# Power.net
KiCad netlist of a schematic drawn in Altium Designer
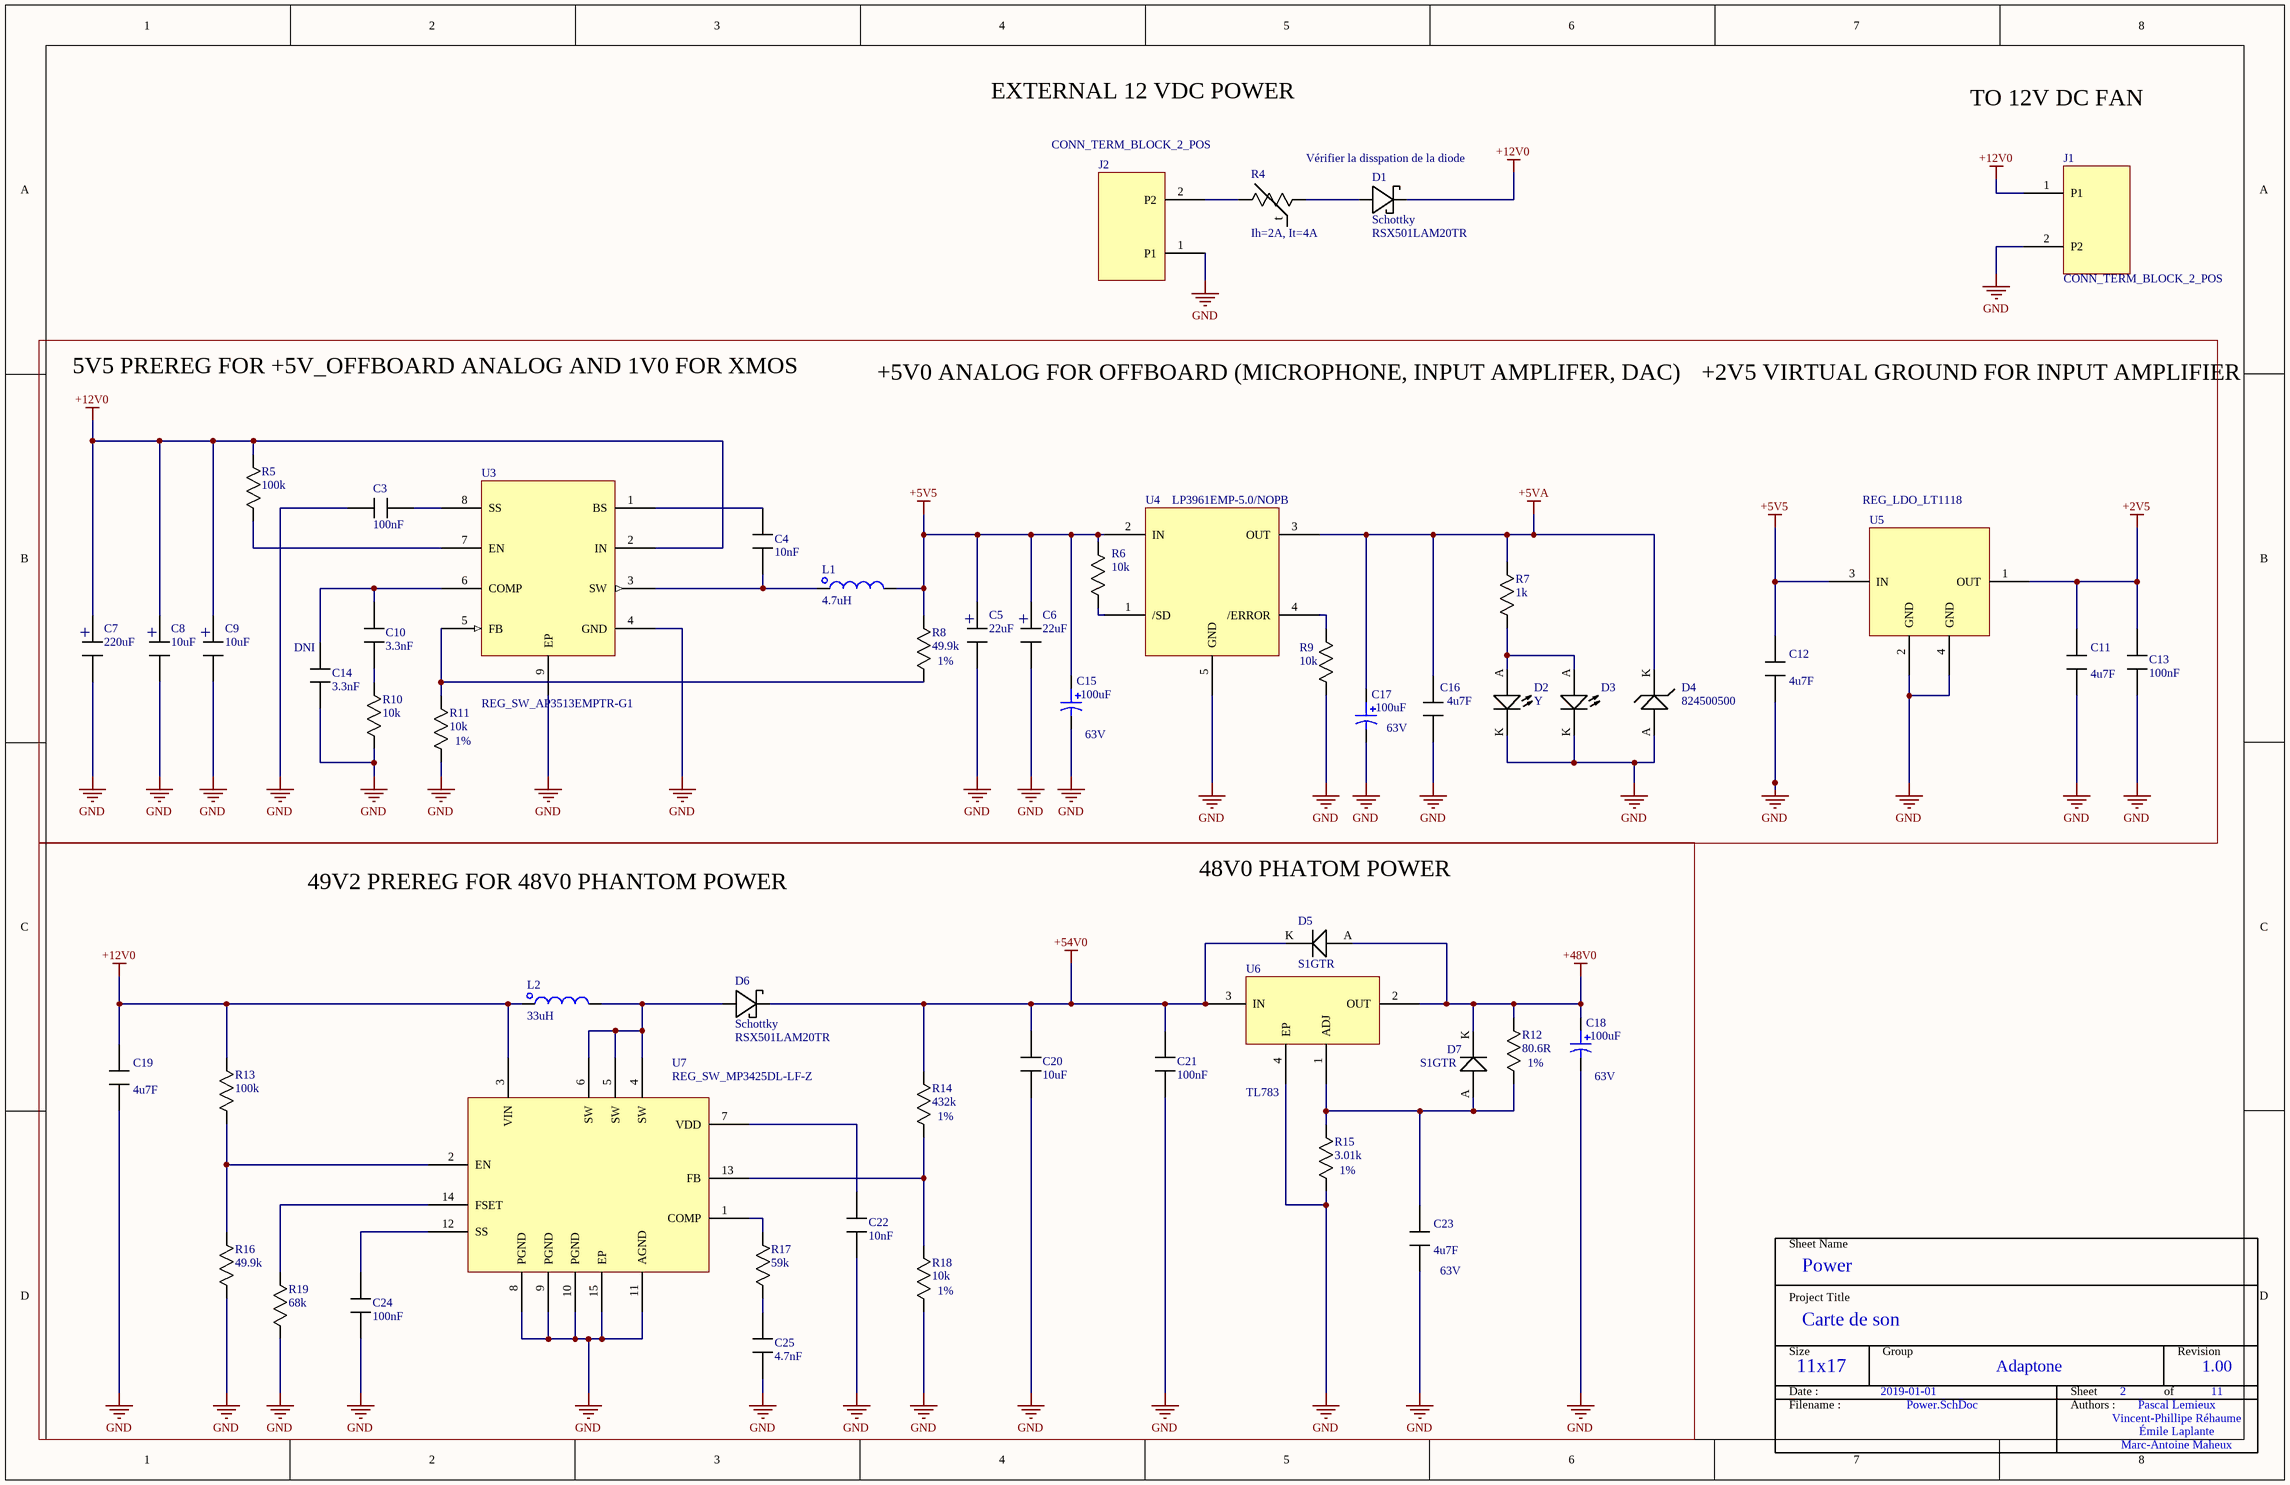
[diagram p0: Power.SchDoc]

(export (version "E")
  (design (tool "Eeschema 10.0.6"))
  (components
    (comp (ref "C3")
      (value "100nF")
      (footprint "0603")
      (description "Capacitor")
      (fields (field (name "MFG") "Samsung"))
      (libsource (lib "ADAPTONE_CARTE_DE_SON") (part "Capacitor"))
    )
    (comp (ref "C4")
      (value "10nF")
      (footprint "0603")
      (description "Capacitor")
      (fields (field (name "MFG") "Samsung"))
      (libsource (lib "ADAPTONE_CARTE_DE_SON") (part "Capacitor"))
    )
    (comp (ref "C5")
      (value "22uF")
      (footprint "CAP_RAD_SMD_DIA157")
      (description "Capacitor")
      (fields (field (name "MFG") "Panasonic") (field (name "Comment") "Capacitor_Polarized"))
      (libsource (lib "ADAPTONE_CARTE_DE_SON") (part "Capacitor_Polarized"))
    )
    (comp (ref "C6")
      (value "22uF")
      (footprint "CAP_RAD_SMD_DIA157")
      (description "Capacitor")
      (fields (field (name "MFG") "Panasonic") (field (name "Comment") "Capacitor_Polarized"))
      (libsource (lib "ADAPTONE_CARTE_DE_SON") (part "Capacitor_Polarized"))
    )
    (comp (ref "C7")
      (value "220uF")
      (footprint "CAP_RAD_SMD_DIA315")
      (description "Capacitor")
      (fields (field (name "MFG") "Nichicon") (field (name "Comment") "Capacitor_Polarized"))
      (libsource (lib "ADAPTONE_CARTE_DE_SON") (part "Capacitor_Polarized_1"))
    )
    (comp (ref "C8")
      (value "10uF")
      (footprint "CAP_RAD_SMD_DIA157")
      (description "Capacitor")
      (fields (field (name "MFG") "Nichicon") (field (name "Comment") "Capacitor_Polarized"))
      (libsource (lib "ADAPTONE_CARTE_DE_SON") (part "Capacitor_Polarized"))
    )
    (comp (ref "C9")
      (value "10uF")
      (footprint "CAP_RAD_SMD_DIA157")
      (description "Capacitor")
      (fields (field (name "MFG") "Nichicon") (field (name "Comment") "Capacitor_Polarized"))
      (libsource (lib "ADAPTONE_CARTE_DE_SON") (part "Capacitor_Polarized"))
    )
    (comp (ref "C10")
      (value "3.3nF")
      (footprint "0603")
      (description "Capacitor")
      (fields (field (name "MFG") "Samsung"))
      (libsource (lib "ADAPTONE_CARTE_DE_SON") (part "Capacitor"))
    )
    (comp (ref "C11")
      (value "4u7F")
      (footprint "0805")
      (description "Capacitor")
      (fields (field (name "MFG") "Samsung"))
      (libsource (lib "ADAPTONE_CARTE_DE_SON") (part "Capacitor"))
    )
    (comp (ref "C12")
      (value "4u7F")
      (footprint "0805")
      (description "Capacitor")
      (fields (field (name "MFG") "Samsung"))
      (libsource (lib "ADAPTONE_CARTE_DE_SON") (part "Capacitor"))
    )
    (comp (ref "C13")
      (value "100nF")
      (footprint "0603")
      (description "Capacitor")
      (fields (field (name "MFG") "Samsung"))
      (libsource (lib "ADAPTONE_CARTE_DE_SON") (part "Capacitor"))
    )
    (comp (ref "C14")
      (value "3.3nF")
      (footprint "0603")
      (description "Capacitor")
      (fields (field (name "MFG") "Samsung") (field (name "NOTE") "DNI"))
      (libsource (lib "ADAPTONE_CARTE_DE_SON") (part "Capacitor"))
    )
    (comp (ref "C15")
      (value "100uF")
      (footprint "CAP_ALU_1010_vishay")
      (description "CAP - ALU 100uF 20% 50V - 1010")
      (fields
        (field (name "MFG") "Nichicon")
        (field (name "MFG PART NUMBER") "UUX1J101MNL1GS")
        (field (name "VOLTAGE") "63V")
        (field (name "CREATEDBY") "Jonathan Bouchard")
      )
      (libsource (lib "S7CAS_Lib2019_REV1_00") (part "CAP_ALU_MAL215099101E3"))
    )
    (comp (ref "C16")
      (value "4u7F")
      (footprint "0603")
      (description "Capacitor")
      (fields (field (name "MFG") "Samsung"))
      (libsource (lib "ADAPTONE_CARTE_DE_SON") (part "Capacitor"))
    )
    (comp (ref "C17")
      (value "100uF")
      (footprint "CAP_ALU_1010_vishay")
      (description "CAP - ALU 100uF 20% 50V - 1010")
      (fields
        (field (name "MFG") "Nichicon")
        (field (name "MFG PART NUMBER") "UUX1J101MNL1GS")
        (field (name "VOLTAGE") "63V")
        (field (name "CREATEDBY") "Jonathan Bouchard")
      )
      (libsource (lib "S7CAS_Lib2019_REV1_00") (part "CAP_ALU_MAL215099101E3"))
    )
    (comp (ref "C18")
      (value "100uF")
      (footprint "CAP_ALU_1010_vishay")
      (description "CAP - ALU 100uF 20% 50V - 1010")
      (fields
        (field (name "MFG") "Nichicon")
        (field (name "MFG PART NUMBER") "UUX1J101MNL1GS")
        (field (name "VOLTAGE") "63V")
        (field (name "CREATEDBY") "Jonathan Bouchard")
      )
      (libsource (lib "S7CAS_Lib2019_REV1_00") (part "CAP_ALU_MAL215099101E3"))
    )
    (comp (ref "C19")
      (value "4u7F")
      (footprint "0805")
      (description "Capacitor")
      (fields (field (name "MFG") "Samsung"))
      (libsource (lib "ADAPTONE_CARTE_DE_SON") (part "Capacitor"))
    )
    (comp (ref "C20")
      (value "10uF")
      (footprint "CAP_1210")
      (description "Capacitor")
      (fields (field (name "MFG") "Samsung"))
      (libsource (lib "LIB_ADAPTONE_PASCAL_LEMIEUX") (part "Capacitor"))
    )
    (comp (ref "C21")
      (value "100nF")
      (footprint "0603")
      (description "Capacitor")
      (fields (field (name "MFG") "Walsin"))
      (libsource (lib "ADAPTONE_CARTE_DE_SON") (part "Capacitor"))
    )
    (comp (ref "C22")
      (value "10nF")
      (footprint "0603")
      (description "Capacitor")
      (fields (field (name "MFG") "Samsung"))
      (libsource (lib "ADAPTONE_CARTE_DE_SON") (part "Capacitor"))
    )
    (comp (ref "C23")
      (value "4u7F")
      (footprint "0603")
      (description "Capacitor")
      (fields (field (name "MFG") "Samsung") (field (name "VOLTAGE") "63V"))
      (libsource (lib "ADAPTONE_CARTE_DE_SON") (part "Capacitor"))
    )
    (comp (ref "C24")
      (value "100nF")
      (footprint "0603")
      (description "Capacitor")
      (fields (field (name "MFG") "Samsung"))
      (libsource (lib "ADAPTONE_CARTE_DE_SON") (part "Capacitor"))
    )
    (comp (ref "C25")
      (value "4.7nF")
      (footprint "0603")
      (description "Capacitor")
      (fields (field (name "MFG") "Samsung"))
      (libsource (lib "ADAPTONE_CARTE_DE_SON") (part "Capacitor"))
    )
    (comp (ref "D1")
      (value "Schottky")
      (footprint "SOD-123F")
      (description "Vf = 390mV, Vr = 20V")
      (fields
        (field (name "MFG") "Rohm Semiconductor")
        (field (name "MFG PART NUMBER") "RSX501LAM20TR")
        (field (name "CREATEDBY") "Emile Laplante")
        (field (name "VERIFIEDBY") "*")
      )
      (libsource (lib "LIB_ADAPTONE_EMILE_LAPLANTE") (part "Schottky"))
    )
    (comp (ref "D2")
      (value "Diode_LED")
      (footprint "0805_LED")
      (description "LED")
      (fields (field (name "MFG") "Osram") (field (name "TYPE") "Y"))
      (libsource (lib "ADAPTONE_CARTE_DE_SON") (part "Diode_LED"))
    )
    (comp (ref "D3")
      (value "Diode_LED")
      (footprint "0805_LED")
      (description "LED")
      (fields (field (name "MFG") "Osram"))
      (libsource (lib "ADAPTONE_CARTE_DE_SON") (part "Diode_LED"))
    )
    (comp (ref "D4")
      (value "Diode_zener")
      (footprint "DIODE_DO-214AC/SMA")
      (description "Diode")
      (fields (field (name "MFG") "Wurth") (field (name "MFG_PN") "824500500"))
      (libsource (lib "ADAPTONE_CARTE_DE_SON") (part "Diode_zener"))
    )
    (comp (ref "D5")
      (value "Diode")
      (footprint "DIODE_SMA")
      (fields (field (name "MFG") "SMC Diode Solutions") (field (name "MFG_PN") "S1GTR"))
      (libsource (lib "ADAPTONE_CARTE_DE_SON") (part "Diode"))
    )
    (comp (ref "D6")
      (value "Schottky")
      (footprint "SOD-123F")
      (description "Vf = 390mV, Vr = 20V")
      (fields
        (field (name "MFG") "Rohm Semiconductor")
        (field (name "MFG PART NUMBER") "RSX501LAM20TR")
        (field (name "CREATEDBY") "Emile Laplante")
        (field (name "VERIFIEDBY") "*")
      )
      (libsource (lib "LIB_ADAPTONE_EMILE_LAPLANTE") (part "Schottky"))
    )
    (comp (ref "D7")
      (value "Diode")
      (footprint "DIODE_SMA")
      (fields (field (name "MFG") "SMC Diode Solutions") (field (name "MFG_PN") "S1GTR"))
      (libsource (lib "ADAPTONE_CARTE_DE_SON") (part "Diode"))
    )
    (comp (ref "J1")
      (value "CONN_TERM_BLOCK_2_POS")
      (footprint "TERM BLOCK")
      (libsource (lib "") (part "CONN_TERM_BLOCK_2_POS_1"))
    )
    (comp (ref "J2")
      (value "CONN_TERM_BLOCK_2_POS")
      (footprint "TERM BLOCK")
      (libsource (lib "LIB_ADAPTONE_EMILE_LAPLANTE") (part "CONN_TERM_BLOCK_2_POS"))
    )
    (comp (ref "L1")
      (value "4.7uH")
      (footprint "IND_252012CDMC/DS")
      (description "Inductor")
      (fields (field (name "MFG") "Bourns Inc."))
      (libsource (lib "ADAPTONE_CARTE_DE_SON") (part "Inductor"))
    )
    (comp (ref "L2")
      (value "33uH")
      (footprint "IND_252012CDMC/DS")
      (description "Inductor")
      (fields (field (name "MFG") "TDK Corporation"))
      (libsource (lib "ADAPTONE_CARTE_DE_SON") (part "Inductor"))
    )
    (comp (ref "R4")
      (value "Ih=2A, It=4A")
      (footprint "1206_PTC")
      (description "Resistor_PTC")
      (fields (field (name "MFG") "Littelfuse Inc."))
      (libsource (lib "ADAPTONE_CARTE_DE_SON") (part "Resistor_PTC"))
    )
    (comp (ref "R5")
      (value "100k")
      (footprint "0603")
      (description "Resistor")
      (fields (field (name "MFG") "Stackpole Electronics Inc"))
      (libsource (lib "ADAPTONE_CARTE_DE_SON") (part "Resistor"))
    )
    (comp (ref "R6")
      (value "10k")
      (footprint "0603")
      (description "Resistor")
      (fields (field (name "MFG") "Yageo"))
      (libsource (lib "ADAPTONE_CARTE_DE_SON") (part "Resistor"))
    )
    (comp (ref "R7")
      (value "1k")
      (footprint "0603")
      (description "Resistor")
      (fields (field (name "MFG") "Yageo"))
      (libsource (lib "ADAPTONE_CARTE_DE_SON") (part "Resistor"))
    )
    (comp (ref "R8")
      (value "49.9k")
      (footprint "0603")
      (description "Resistor")
      (fields (field (name "MFG") "Yageo") (field (name "TOLERANCE") "1%"))
      (libsource (lib "ADAPTONE_CARTE_DE_SON") (part "Resistor"))
    )
    (comp (ref "R9")
      (value "10k")
      (footprint "0603")
      (description "Resistor")
      (fields (field (name "MFG") "Yageo"))
      (libsource (lib "ADAPTONE_CARTE_DE_SON") (part "Resistor"))
    )
    (comp (ref "R10")
      (value "10k")
      (footprint "0603")
      (description "Resistor")
      (fields (field (name "MFG") "Yageo"))
      (libsource (lib "ADAPTONE_CARTE_DE_SON") (part "Resistor"))
    )
    (comp (ref "R11")
      (value "10k")
      (footprint "0603")
      (description "Resistor")
      (fields (field (name "MFG") "Stackpole Electronics Inc") (field (name "TOLERANCE") "1%"))
      (libsource (lib "ADAPTONE_CARTE_DE_SON") (part "Resistor"))
    )
    (comp (ref "R12")
      (value "80.6R")
      (footprint "0603")
      (description "Resistor")
      (fields (field (name "MFG") "Stackpole Electronics Inc") (field (name "TOLERANCE") "1%"))
      (libsource (lib "ADAPTONE_CARTE_DE_SON") (part "Resistor"))
    )
    (comp (ref "R13")
      (value "100k")
      (footprint "0603")
      (description "Resistor")
      (fields (field (name "MFG") "Stackpole Electronics Inc"))
      (libsource (lib "ADAPTONE_CARTE_DE_SON") (part "Resistor"))
    )
    (comp (ref "R14")
      (value "432k")
      (footprint "0603")
      (description "Resistor")
      (fields (field (name "MFG") "Yageo") (field (name "TOLERANCE") "1%"))
      (libsource (lib "ADAPTONE_CARTE_DE_SON") (part "Resistor"))
    )
    (comp (ref "R15")
      (value "3.01k")
      (footprint "0603")
      (description "Resistor")
      (fields (field (name "MFG") "Panasonic Electronic Components") (field (name "TOLERANCE") "1%"))
      (libsource (lib "ADAPTONE_CARTE_DE_SON") (part "Resistor"))
    )
    (comp (ref "R16")
      (value "49.9k")
      (footprint "0603")
      (description "Resistor")
      (fields (field (name "MFG") "Yageo"))
      (libsource (lib "ADAPTONE_CARTE_DE_SON") (part "Resistor"))
    )
    (comp (ref "R17")
      (value "59k")
      (footprint "0603")
      (description "Resistor")
      (fields (field (name "MFG") "Stackpole Electronics Inc"))
      (libsource (lib "ADAPTONE_CARTE_DE_SON") (part "Resistor"))
    )
    (comp (ref "R18")
      (value "10k")
      (footprint "0603")
      (description "Resistor")
      (fields (field (name "MFG") "Stackpole Electronics Inc") (field (name "TOLERANCE") "1%"))
      (libsource (lib "ADAPTONE_CARTE_DE_SON") (part "Resistor"))
    )
    (comp (ref "R19")
      (value "68k")
      (footprint "0603")
      (description "Resistor")
      (fields (field (name "MFG") "Yageo"))
      (libsource (lib "ADAPTONE_CARTE_DE_SON") (part "Resistor"))
    )
    (comp (ref "U3")
      (value "REG_SW_AP3513EMPTR-G1")
      (footprint "AP3513EMPTR-G1")
      (fields
        (field (name "MFG") "Diodes Incorporated")
        (field (name "MFG PART NUMBER") "AP3513EMPTR-G1")
        (field (name "CREATEDBY") "Emile Laplante")
        (field (name "VERIFIEDBY") "*")
      )
      (libsource (lib "LIB_ADAPTONE_EMILE_LAPLANTE") (part "REG_SW_AP3513EMPTR-G1"))
    )
    (comp (ref "U4")
      (value "LP3961EMP-5.0/NOPB")
      (footprint "TL783")
      (fields
        (field (name "MFG") "Texas Instruments")
        (field (name "CREATEDBY") "Emile Laplante")
        (field (name "VERIFIEDBY") "*")
      )
      (libsource (lib "LIB_ADAPTONE_EMILE_LAPLANTE") (part "LP3961EMP-5.0/NOPB"))
    )
    (comp (ref "U5")
      (value "REG_LDO_LT1118")
      (footprint "SOT-223-3")
      (fields
        (field (name "MFG") "Linear Technology/Analog Devices")
        (field (name "MFG PART NUMBER") "LT1118CST-2.5#PBF")
        (field (name "CREATEDBY") "Emile Laplante")
        (field (name "VERIFIEDBY") "*")
      )
      (libsource (lib "LIB_ADAPTONE_EMILE_LAPLANTE") (part "REG_LDO_LT1118"))
    )
    (comp (ref "U6")
      (value "TL783")
      (footprint "TL783")
      (fields
        (field (name "MFG") "Texas Instruments")
        (field (name "MFG PART NUMBER") "TL783CKTTR")
        (field (name "CREATEDBY") "Emile Laplante")
        (field (name "VERIFIEDBY") "*")
      )
      (libsource (lib "LIB_ADAPTONE_EMILE_LAPLANTE") (part "TL783"))
    )
    (comp (ref "U7")
      (value "REG_SW_MP3425DL-LF-Z")
      (footprint "14-VFDFN Exposed Pad")
      (fields
        (field (name "MFG") "Monolithic Power Systems Inc.")
        (field (name "MFG PART NUMBER") "MP3425DL-LF-Z")
        (field (name "CREATEDBY") "Emile Laplante")
        (field (name "VERIFIEDBY") "*")
      )
      (libsource (lib "LIB_ADAPTONE_EMILE_LAPLANTE") (part "REG_SW_MP3425DL-LF-Z"))
    )
  )
  (nets
    (net (code "1") (name "+2V5") (class "Default")
      (node (ref "C11") (pin "1") (pintype "passive"))
      (node (ref "C13") (pin "2") (pintype "passive"))
      (node (ref "U5") (pin "1") (pinfunction "OUT_1") (pintype "passive"))
    )
    (net (code "2") (name "+5V5") (class "Default")
      (node (ref "C12") (pin "1") (pintype "passive"))
      (node (ref "C15") (pin "1") (pinfunction "1_1") (pintype "passive"))
      (node (ref "C5") (pin "+") (pintype "passive"))
      (node (ref "C6") (pin "+") (pintype "passive"))
      (node (ref "L1") (pin "2") (pintype "passive"))
      (node (ref "R6") (pin "1") (pintype "passive"))
      (node (ref "R8") (pin "1") (pintype "passive"))
      (node (ref "U4") (pin "2") (pinfunction "IN_2") (pintype "passive"))
      (node (ref "U5") (pin "3") (pinfunction "IN_3") (pintype "passive"))
    )
    (net (code "3") (name "+5VA") (class "Default")
      (node (ref "C16") (pin "1") (pintype "passive"))
      (node (ref "C17") (pin "1") (pinfunction "1_1") (pintype "passive"))
      (node (ref "D4") (pin "K") (pintype "passive"))
      (node (ref "R7") (pin "2") (pintype "passive"))
      (node (ref "U4") (pin "3") (pinfunction "OUT_3") (pintype "passive"))
    )
    (net (code "4") (name "+12V0") (class "Default")
      (node (ref "C19") (pin "1") (pintype "passive"))
      (node (ref "C7") (pin "+") (pintype "passive"))
      (node (ref "C8") (pin "+") (pintype "passive"))
      (node (ref "C9") (pin "+") (pintype "passive"))
      (node (ref "D1") (pin "2") (pinfunction "cathode_2") (pintype "passive"))
      (node (ref "J1") (pin "1") (pinfunction "P1_1") (pintype "passive"))
      (node (ref "L2") (pin "1") (pintype "passive"))
      (node (ref "R13") (pin "2") (pintype "passive"))
      (node (ref "R5") (pin "2") (pintype "passive"))
      (node (ref "U3") (pin "2") (pinfunction "IN_2") (pintype "power_in"))
      (node (ref "U7") (pin "3") (pinfunction "VIN_3") (pintype "passive"))
    )
    (net (code "5") (name "+48V0") (class "Default")
      (node (ref "C18") (pin "1") (pinfunction "1_1") (pintype "passive"))
      (node (ref "D5") (pin "A") (pintype "passive"))
      (node (ref "D7") (pin "K") (pintype "passive"))
      (node (ref "R12") (pin "1") (pintype "passive"))
      (node (ref "U6") (pin "2") (pinfunction "OUT_2") (pintype "passive"))
    )
    (net (code "6") (name "+54V0") (class "Default")
      (node (ref "C20") (pin "1") (pintype "passive"))
      (node (ref "C21") (pin "2") (pintype "passive"))
      (node (ref "D5") (pin "K") (pintype "passive"))
      (node (ref "D6") (pin "2") (pinfunction "cathode_2") (pintype "passive"))
      (node (ref "R14") (pin "1") (pintype "passive"))
      (node (ref "U6") (pin "3") (pinfunction "IN_3") (pintype "passive"))
    )
    (net (code "7") (name "GND") (class "Default")
      (node (ref "C11") (pin "2") (pintype "passive"))
      (node (ref "C12") (pin "2") (pintype "passive"))
      (node (ref "C13") (pin "1") (pintype "passive"))
      (node (ref "C14") (pin "2") (pintype "passive"))
      (node (ref "C15") (pin "2") (pinfunction "2_2") (pintype "passive"))
      (node (ref "C16") (pin "2") (pintype "passive"))
      (node (ref "C17") (pin "2") (pinfunction "2_2") (pintype "passive"))
      (node (ref "C18") (pin "2") (pinfunction "2_2") (pintype "passive"))
      (node (ref "C19") (pin "2") (pintype "passive"))
      (node (ref "C20") (pin "2") (pintype "passive"))
      (node (ref "C21") (pin "1") (pintype "passive"))
      (node (ref "C22") (pin "2") (pintype "passive"))
      (node (ref "C23") (pin "2") (pintype "passive"))
      (node (ref "C24") (pin "1") (pintype "passive"))
      (node (ref "C25") (pin "2") (pintype "passive"))
      (node (ref "C3") (pin "1") (pintype "passive"))
      (node (ref "C5") (pin "-") (pintype "passive"))
      (node (ref "C6") (pin "-") (pintype "passive"))
      (node (ref "C7") (pin "-") (pintype "passive"))
      (node (ref "C8") (pin "-") (pintype "passive"))
      (node (ref "C9") (pin "-") (pintype "passive"))
      (node (ref "D2") (pin "K") (pintype "passive"))
      (node (ref "D3") (pin "K") (pintype "passive"))
      (node (ref "D4") (pin "A") (pintype "passive"))
      (node (ref "J1") (pin "2") (pinfunction "P2_2") (pintype "passive"))
      (node (ref "J2") (pin "1") (pinfunction "P1_1") (pintype "passive"))
      (node (ref "R10") (pin "2") (pintype "passive"))
      (node (ref "R11") (pin "2") (pintype "passive"))
      (node (ref "R15") (pin "2") (pintype "passive"))
      (node (ref "R16") (pin "2") (pintype "passive"))
      (node (ref "R18") (pin "2") (pintype "passive"))
      (node (ref "R19") (pin "1") (pintype "passive"))
      (node (ref "R9") (pin "2") (pintype "passive"))
      (node (ref "U3") (pin "4") (pinfunction "GND_4") (pintype "passive"))
      (node (ref "U3") (pin "9") (pinfunction "EP_9") (pintype "passive"))
      (node (ref "U4") (pin "5") (pinfunction "GND_5") (pintype "passive"))
      (node (ref "U5") (pin "2") (pinfunction "GND_2") (pintype "passive"))
      (node (ref "U5") (pin "4") (pinfunction "GND_4") (pintype "passive"))
      (node (ref "U6") (pin "4") (pinfunction "EP_4") (pintype "passive"))
      (node (ref "U7") (pin "10") (pinfunction "PGND_10") (pintype "passive"))
      (node (ref "U7") (pin "11") (pinfunction "AGND_11") (pintype "passive"))
      (node (ref "U7") (pin "15") (pinfunction "EP_15") (pintype "passive"))
      (node (ref "U7") (pin "8") (pinfunction "PGND_8") (pintype "passive"))
      (node (ref "U7") (pin "9") (pinfunction "PGND_9") (pintype "passive"))
    )
    (net (code "8") (name "Net-(C10-Pad2)") (class "Default")
      (node (ref "C10") (pin "2") (pintype "passive"))
      (node (ref "R10") (pin "1") (pintype "passive"))
    )
    (net (code "9") (name "Net-(C25-Pad1)") (class "Default")
      (node (ref "C25") (pin "1") (pintype "passive"))
      (node (ref "R17") (pin "2") (pintype "passive"))
    )
    (net (code "10") (name "Net-(D1-anode)") (class "Default")
      (node (ref "D1") (pin "1") (pinfunction "anode_1") (pintype "passive"))
      (node (ref "R4") (pin "2") (pintype "passive"))
    )
    (net (code "11") (name "Net-(D2-PadA)") (class "Default")
      (node (ref "D2") (pin "A") (pintype "passive"))
      (node (ref "D3") (pin "A") (pintype "passive"))
      (node (ref "R7") (pin "1") (pintype "passive"))
    )
    (net (code "12") (name "Net-(D6-anode)") (class "Default")
      (node (ref "D6") (pin "1") (pinfunction "anode_1") (pintype "passive"))
      (node (ref "L2") (pin "2") (pintype "passive"))
      (node (ref "U7") (pin "4") (pinfunction "SW_4") (pintype "passive"))
      (node (ref "U7") (pin "5") (pinfunction "SW_5") (pintype "passive"))
      (node (ref "U7") (pin "6") (pinfunction "SW_6") (pintype "passive"))
    )
    (net (code "13") (name "Net-(J2-P2)") (class "Default")
      (node (ref "J2") (pin "2") (pinfunction "P2_2") (pintype "passive"))
      (node (ref "R4") (pin "1") (pintype "passive"))
    )
    (net (code "14") (name "Net-(U3-BS)") (class "Default")
      (node (ref "C4") (pin "1") (pintype "passive"))
      (node (ref "U3") (pin "1") (pinfunction "BS_1") (pintype "passive"))
    )
    (net (code "15") (name "Net-(U3-COMP)") (class "Default")
      (node (ref "C10") (pin "1") (pintype "passive"))
      (node (ref "C14") (pin "1") (pintype "passive"))
      (node (ref "U3") (pin "6") (pinfunction "COMP_6") (pintype "passive"))
    )
    (net (code "16") (name "Net-(U3-EN)") (class "Default")
      (node (ref "R5") (pin "1") (pintype "passive"))
      (node (ref "U3") (pin "7") (pinfunction "EN_7") (pintype "passive"))
    )
    (net (code "17") (name "Net-(U3-FB)") (class "Default")
      (node (ref "R11") (pin "1") (pintype "passive"))
      (node (ref "R8") (pin "2") (pintype "passive"))
      (node (ref "U3") (pin "5") (pinfunction "FB_5") (pintype "input"))
    )
    (net (code "18") (name "Net-(U3-SS)") (class "Default")
      (node (ref "C3") (pin "2") (pintype "passive"))
      (node (ref "U3") (pin "8") (pinfunction "SS_8") (pintype "passive"))
    )
    (net (code "19") (name "Net-(U3-SW)") (class "Default")
      (node (ref "C4") (pin "2") (pintype "passive"))
      (node (ref "L1") (pin "1") (pintype "passive"))
      (node (ref "U3") (pin "3") (pinfunction "SW_3") (pintype "output"))
    )
    (net (code "20") (name "Net-(U4-{slash}ERROR)") (class "Default")
      (node (ref "R9") (pin "1") (pintype "passive"))
      (node (ref "U4") (pin "4") (pinfunction "/ERROR_4") (pintype "passive"))
    )
    (net (code "21") (name "Net-(U4-{slash}SD)") (class "Default")
      (node (ref "R6") (pin "2") (pintype "passive"))
      (node (ref "U4") (pin "1") (pinfunction "/SD_1") (pintype "passive"))
    )
    (net (code "22") (name "Net-(U6-ADJ)") (class "Default")
      (node (ref "C23") (pin "1") (pintype "passive"))
      (node (ref "D7") (pin "A") (pintype "passive"))
      (node (ref "R12") (pin "2") (pintype "passive"))
      (node (ref "R15") (pin "1") (pintype "passive"))
      (node (ref "U6") (pin "1") (pinfunction "ADJ_1") (pintype "passive"))
    )
    (net (code "23") (name "Net-(U7-COMP)") (class "Default")
      (node (ref "R17") (pin "1") (pintype "passive"))
      (node (ref "U7") (pin "1") (pinfunction "COMP_1") (pintype "passive"))
    )
    (net (code "24") (name "Net-(U7-EN)") (class "Default")
      (node (ref "R13") (pin "1") (pintype "passive"))
      (node (ref "R16") (pin "1") (pintype "passive"))
      (node (ref "U7") (pin "2") (pinfunction "EN_2") (pintype "passive"))
    )
    (net (code "25") (name "Net-(U7-FB)") (class "Default")
      (node (ref "R14") (pin "2") (pintype "passive"))
      (node (ref "R18") (pin "1") (pintype "passive"))
      (node (ref "U7") (pin "13") (pinfunction "FB_13") (pintype "passive"))
    )
    (net (code "26") (name "Net-(U7-FSET)") (class "Default")
      (node (ref "R19") (pin "2") (pintype "passive"))
      (node (ref "U7") (pin "14") (pinfunction "FSET_14") (pintype "passive"))
    )
    (net (code "27") (name "Net-(U7-SS)") (class "Default")
      (node (ref "C24") (pin "2") (pintype "passive"))
      (node (ref "U7") (pin "12") (pinfunction "SS_12") (pintype "passive"))
    )
    (net (code "28") (name "Net-(U7-VDD)") (class "Default")
      (node (ref "C22") (pin "1") (pintype "passive"))
      (node (ref "U7") (pin "7") (pinfunction "VDD_7") (pintype "passive"))
    )
  )
)
